# Battery_Charger.net
KiCad netlist of a schematic drawn in Altium Designer
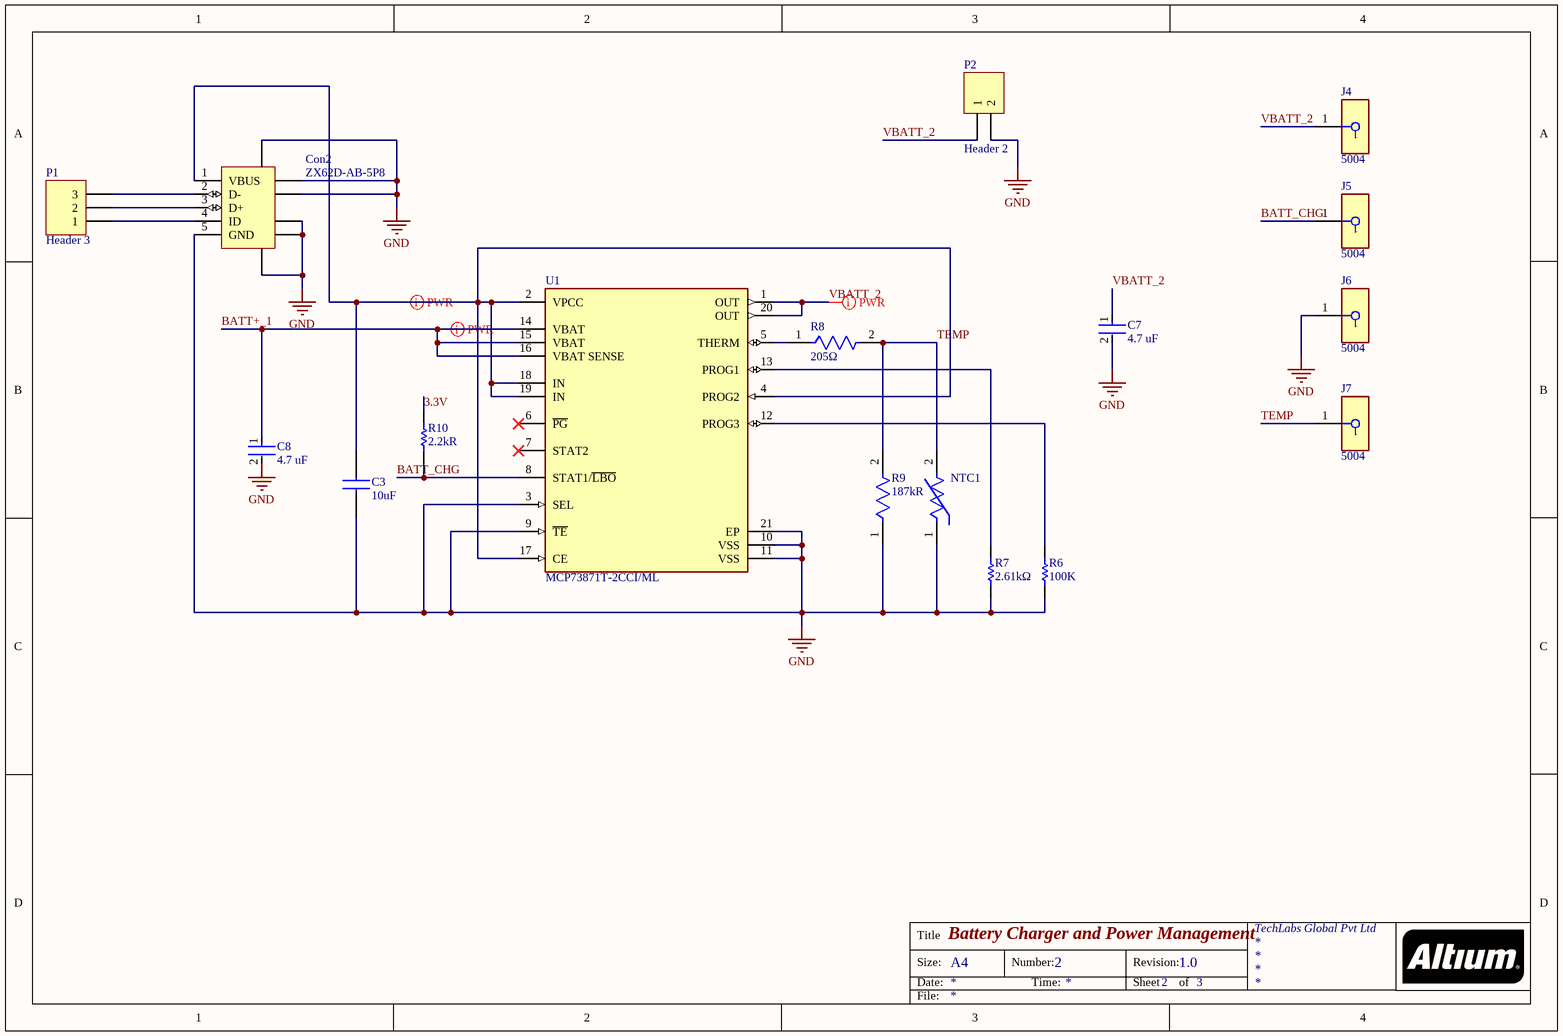
[diagram p0: Battery_Charger.SchDoc]

(export (version "E")
  (design (tool "Eeschema 10.0.6"))
  (components
    (comp (ref "C3")
      (value "10uF")
      (footprint "CAPC1005X70N")
      (description "CAP CER 10UF 6.3V X5R 0402")
      (fields
        (field (name "MANUFACTURER") "Samsung Electro-Mechanics")
        (field (name "MFR. PART #") "CL05A106MQ5NUNC")
      )
      (libsource (lib "CL05A106MQ5NUNC") (part "CL05A106MQ5NUNC"))
    )
    (comp (ref "C7")
      (value "4.7 uF")
      (footprint "FP-CC0402-MFG")
      (description "CAP CER 4.7UF 6.3V X5R 0402")
      (fields
        (field (name "OCTOPART") "https://octopart.com/cc0402mrx5r5bb475-yageo-20021081")
        (field (name "MANUFACTURER") "YAGEO")
      )
      (libsource (lib "Altium Content Vault") (part "11868f565c42a9108669ba33697ecf6"))
    )
    (comp (ref "C8")
      (value "4.7 uF")
      (footprint "FP-CC0402-MFG")
      (description "CAP CER 4.7UF 6.3V X5R 0402")
      (fields
        (field (name "OCTOPART") "https://octopart.com/cc0402mrx5r5bb475-yageo-20021081")
        (field (name "MANUFACTURER") "YAGEO")
      )
      (libsource (lib "Altium Content Vault") (part "11868f565c42a9108669ba33697ecf6"))
    )
    (comp (ref "Con2")
      (value "ZX62D-AB-5P8")
      (footprint "HIRO-ZX62D-AB-5P8_V")
      (fields
        (field (name "MFR. PART #") "ZX62D-AB-5P8(30)")
        (field (name "MANUFACTURER") "Hirose Electric")
        (field (name "LCSC PART #") "C598206")
      )
      (libsource (lib "Altium Content Vault") (part "HIRO-ZX62D-AB-5P8-5"))
    )
    (comp (ref "J4")
      (value "5004")
      (footprint "FP-5004-MFG")
      (description "PC TEST POINT MINIATURE YELLOW")
      (fields
        (field (name "MANUFACTURER") "Keystone")
        (field (name "OCTOPART") "https://octopart.com/5004-keystone-28591")
      )
      (libsource (lib "Altium Content Vault") (part "98815daf2f2c152b0c43f5ab9800df6"))
    )
    (comp (ref "J5")
      (value "5004")
      (footprint "FP-5004-MFG")
      (description "PC TEST POINT MINIATURE YELLOW")
      (fields
        (field (name "MANUFACTURER") "Keystone")
        (field (name "OCTOPART") "https://octopart.com/5004-keystone-28591")
      )
      (libsource (lib "Altium Content Vault") (part "98815daf2f2c152b0c43f5ab9800df6"))
    )
    (comp (ref "J6")
      (value "5004")
      (footprint "FP-5004-MFG")
      (description "PC TEST POINT MINIATURE YELLOW")
      (fields
        (field (name "MANUFACTURER") "Keystone")
        (field (name "OCTOPART") "https://octopart.com/5004-keystone-28591")
      )
      (libsource (lib "Altium Content Vault") (part "98815daf2f2c152b0c43f5ab9800df6"))
    )
    (comp (ref "J7")
      (value "5004")
      (footprint "FP-5004-MFG")
      (description "PC TEST POINT MINIATURE YELLOW")
      (fields
        (field (name "MANUFACTURER") "Keystone")
        (field (name "OCTOPART") "https://octopart.com/5004-keystone-28591")
      )
      (libsource (lib "Altium Content Vault") (part "98815daf2f2c152b0c43f5ab9800df6"))
    )
    (comp (ref "NTC1")
      (value "NTC 10K Radial Leaded")
      (footprint "FP-NXR_151B030-MFG")
      (description "NTC Thermistors ±1% 7.5mW 3380K ±1% 10kΩ Radial Leaded NTC Thermistors ROHS")
      (fields (field (name "TOLERANCE") "1%") (field (name "LCSC PART #") "C152559"))
      (libsource (lib "Altium Content Vault") (part "3b148a6ebabc5fb4d708a66c052d352"))
    )
    (comp (ref "P1")
      (value "Header 3")
      (footprint "HDR1X3")
      (description "Header, 3-Pin")
      (fields (field (name "PUBLISHER") "Altium Limited"))
      (libsource (lib "Miscellaneous Connectors") (part "Header 3"))
    )
    (comp (ref "P2")
      (value "Header 2")
      (footprint "HDR1X2")
      (description "Header, 2-Pin")
      (fields (field (name "PUBLISHER") "Altium Limited"))
      (libsource (lib "Miscellaneous Connectors") (part "Header 2"))
    )
    (comp (ref "R6")
      (value "100K")
      (footprint "RESC1005X40X25NL05T10")
      (description "100K ±1% 1/16W 0402 Chip Resistor - Surface Mount RoHS")
      (fields (field (name "MANUFACTURER") "Yageo / Phycomp") (field (name "LCSC PART #") "Tolerance"))
      (libsource (lib "Altium Content Vault") (part "RES"))
    )
    (comp (ref "R7")
      (value "2.61kΩ")
      (footprint "RESC1005X40X25NL05T10")
      (fields
        (field (name "MANUFACTURER") "Yageo / Phycomp")
        (field (name "MFR. PART #") "RC0402FR-072K61L")
        (field (name "LCSC PART #") "C163472")
      )
      (libsource (lib "Altium Content Vault") (part "RES"))
    )
    (comp (ref "R8")
      (value "205Ω")
      (footprint "FP-RT0402-MFG")
      (description "205Ω 50V ±50ppm/℃ -55℃~+155℃ ±1% Thin Film Resistor 62.5mW 0402 Chip Resistor - Surface Mount ROHS")
      (fields
        (field (name "OCTOPART") "https://octopart.com/rt0402fre07205rl-yageo-1208039")
        (field (name "TOLERANCE") "0.01")
      )
      (libsource (lib "Altium Content Vault") (part "1029c3af85768c4190bb7ad29bc67b5"))
    )
    (comp (ref "R9")
      (value "187kR")
      (footprint "FP-AC0402-MFG")
      (fields
        (field (name "TOLERANCE") "1%")
        (field (name "MANUFACTURER") "YAGEO")
        (field (name "LCSC PART #") "C226824")
      )
      (libsource (lib "Altium Content Vault") (part "1029c3af85768c4190bb7ad29bc67b5"))
    )
    (comp (ref "R10")
      (value "2.2kR")
      (footprint "RESC1005X40X25ML05T10")
      (fields
        (field (name "MANUFACTURER") "Yageo / Phycomp")
        (field (name "MFR. PART #") "RC0402FR-072K2L")
        (field (name "LCSC PART #") "C114762")
      )
      (libsource (lib "Altium Content Vault") (part "RES"))
    )
    (comp (ref "U1")
      (value "MCP73871T-2CCI/ML")
      (footprint "FP-C04-126-IPC_C")
      (description "IC USB/AC BATT CHRGR W/PPM 20QFN")
      (fields
        (field (name "MANUFACTURER") "Microchip Technology")
        (field (name "DIGI-KEY PART #") "MCP73871T-2CCI/MLTR-ND")
      )
      (libsource (lib "Altium Content Vault") (part "b0f216601a400a2976e0698385bc2c7"))
    )
  )
  (nets
    (net (code "1") (name "/3.3V") (class "Default")
      (node (ref "R10") (pin "2") (pinfunction "2_2") (pintype "passive"))
    )
    (net (code "2") (name "/BATT+_1") (class "Default")
      (node (ref "C8") (pin "1") (pinfunction "1_1") (pintype "passive"))
      (node (ref "U1") (pin "14") (pinfunction "VBAT_14") (pintype "power_in"))
      (node (ref "U1") (pin "15") (pinfunction "VBAT_15") (pintype "power_in"))
      (node (ref "U1") (pin "16") (pinfunction "VBAT_SENSE_16") (pintype "power_in"))
    )
    (net (code "3") (name "/BATT_CHG") (class "Default")
      (node (ref "J5") (pin "1") (pinfunction "1_1") (pintype "passive"))
      (node (ref "R10") (pin "1") (pinfunction "1_1") (pintype "passive"))
      (node (ref "U1") (pin "8") (pinfunction "STAT1/~{LBO}_8") (pintype "open_collector"))
    )
    (net (code "4") (name "/TEMP") (class "Default")
      (node (ref "J7") (pin "1") (pinfunction "1_1") (pintype "passive"))
      (node (ref "NTC1") (pin "2") (pinfunction "2_2") (pintype "passive"))
      (node (ref "R8") (pin "2") (pinfunction "2_2") (pintype "passive"))
      (node (ref "R9") (pin "2") (pinfunction "2_2") (pintype "passive"))
    )
    (net (code "5") (name "/VBATT_2") (class "Default")
      (node (ref "C7") (pin "1") (pinfunction "1_1") (pintype "passive"))
      (node (ref "J4") (pin "1") (pinfunction "1_1") (pintype "passive"))
      (node (ref "P2") (pin "1") (pinfunction "1_1") (pintype "passive"))
      (node (ref "U1") (pin "1") (pinfunction "OUT_1") (pintype "output"))
      (node (ref "U1") (pin "20") (pinfunction "OUT_20") (pintype "output"))
    )
    (net (code "6") (name "GND") (class "Default")
      (node (ref "C3") (pin "1") (pinfunction "1_1") (pintype "passive"))
      (node (ref "C7") (pin "2") (pinfunction "2_2") (pintype "passive"))
      (node (ref "C8") (pin "2") (pinfunction "2_2") (pintype "passive"))
      (node (ref "Con2") (pin "10") (pinfunction "SHLD_10") (pintype "passive"))
      (node (ref "Con2") (pin "11") (pinfunction "SHLD_11") (pintype "passive"))
      (node (ref "Con2") (pin "5") (pinfunction "GND_5") (pintype "power_in"))
      (node (ref "Con2") (pin "6") (pinfunction "SHLD_6") (pintype "passive"))
      (node (ref "Con2") (pin "7") (pinfunction "SHLD_7") (pintype "passive"))
      (node (ref "Con2") (pin "8") (pinfunction "SHLD_8") (pintype "passive"))
      (node (ref "Con2") (pin "9") (pinfunction "SHLD_9") (pintype "passive"))
      (node (ref "J6") (pin "1") (pinfunction "1_1") (pintype "passive"))
      (node (ref "NTC1") (pin "1") (pinfunction "1_1") (pintype "passive"))
      (node (ref "P2") (pin "2") (pinfunction "2_2") (pintype "passive"))
      (node (ref "R6") (pin "1") (pinfunction "1_1") (pintype "passive"))
      (node (ref "R7") (pin "1") (pinfunction "1_1") (pintype "passive"))
      (node (ref "R9") (pin "1") (pinfunction "1_1") (pintype "passive"))
      (node (ref "U1") (pin "10") (pinfunction "VSS_10") (pintype "power_in"))
      (node (ref "U1") (pin "11") (pinfunction "VSS_11") (pintype "power_in"))
      (node (ref "U1") (pin "21") (pinfunction "EP_21") (pintype "passive"))
      (node (ref "U1") (pin "3") (pinfunction "SEL_3") (pintype "input"))
      (node (ref "U1") (pin "9") (pinfunction "~{TE}_9") (pintype "input"))
    )
    (net (code "7") (name "Net-(Con2-D+)") (class "Default")
      (node (ref "Con2") (pin "3") (pinfunction "D+_3") (pintype "bidirectional"))
      (node (ref "P1") (pin "2") (pinfunction "2_2") (pintype "passive"))
    )
    (net (code "8") (name "Net-(Con2-D-)") (class "Default")
      (node (ref "Con2") (pin "2") (pinfunction "D-_2") (pintype "bidirectional"))
      (node (ref "P1") (pin "3") (pinfunction "3_3") (pintype "passive"))
    )
    (net (code "9") (name "Net-(Con2-ID)") (class "Default")
      (node (ref "Con2") (pin "4") (pinfunction "ID_4") (pintype "passive"))
      (node (ref "P1") (pin "1") (pinfunction "1_1") (pintype "passive"))
    )
    (net (code "10") (name "Net-(Con2-VBUS)") (class "Default")
      (node (ref "C3") (pin "2") (pinfunction "2_2") (pintype "passive"))
      (node (ref "Con2") (pin "1") (pinfunction "VBUS_1") (pintype "power_in"))
      (node (ref "U1") (pin "17") (pinfunction "CE_17") (pintype "input"))
      (node (ref "U1") (pin "18") (pinfunction "IN_18") (pintype "power_in"))
      (node (ref "U1") (pin "19") (pinfunction "IN_19") (pintype "power_in"))
      (node (ref "U1") (pin "2") (pinfunction "VPCC_2") (pintype "power_in"))
      (node (ref "U1") (pin "4") (pinfunction "PROG2_4") (pintype "input"))
    )
    (net (code "11") (name "Net-(U1-PROG1)") (class "Default")
      (node (ref "R7") (pin "2") (pinfunction "2_2") (pintype "passive"))
      (node (ref "U1") (pin "13") (pinfunction "PROG1_13") (pintype "bidirectional"))
    )
    (net (code "12") (name "Net-(U1-PROG3)") (class "Default")
      (node (ref "R6") (pin "2") (pinfunction "2_2") (pintype "passive"))
      (node (ref "U1") (pin "12") (pinfunction "PROG3_12") (pintype "bidirectional"))
    )
    (net (code "13") (name "Net-(U1-THERM)") (class "Default")
      (node (ref "R8") (pin "1") (pinfunction "1_1") (pintype "passive"))
      (node (ref "U1") (pin "5") (pinfunction "THERM_5") (pintype "bidirectional"))
    )
    (net (code "14") (name "unconnected-(U1-STAT2-Pad7)") (class "Default")
      (node (ref "U1") (pin "7") (pinfunction "STAT2_7") (pintype "open_collector+no_connect"))
    )
    (net (code "15") (name "unconnected-(U1-~{PG}-Pad6)") (class "Default")
      (node (ref "U1") (pin "6") (pinfunction "~{PG}_6") (pintype "open_collector+no_connect"))
    )
  )
)
